# SCH_M5_Stick_YellowBox_Hat_2023-08-26.net
KiCad netlist of a schematic drawn in EasyEDA
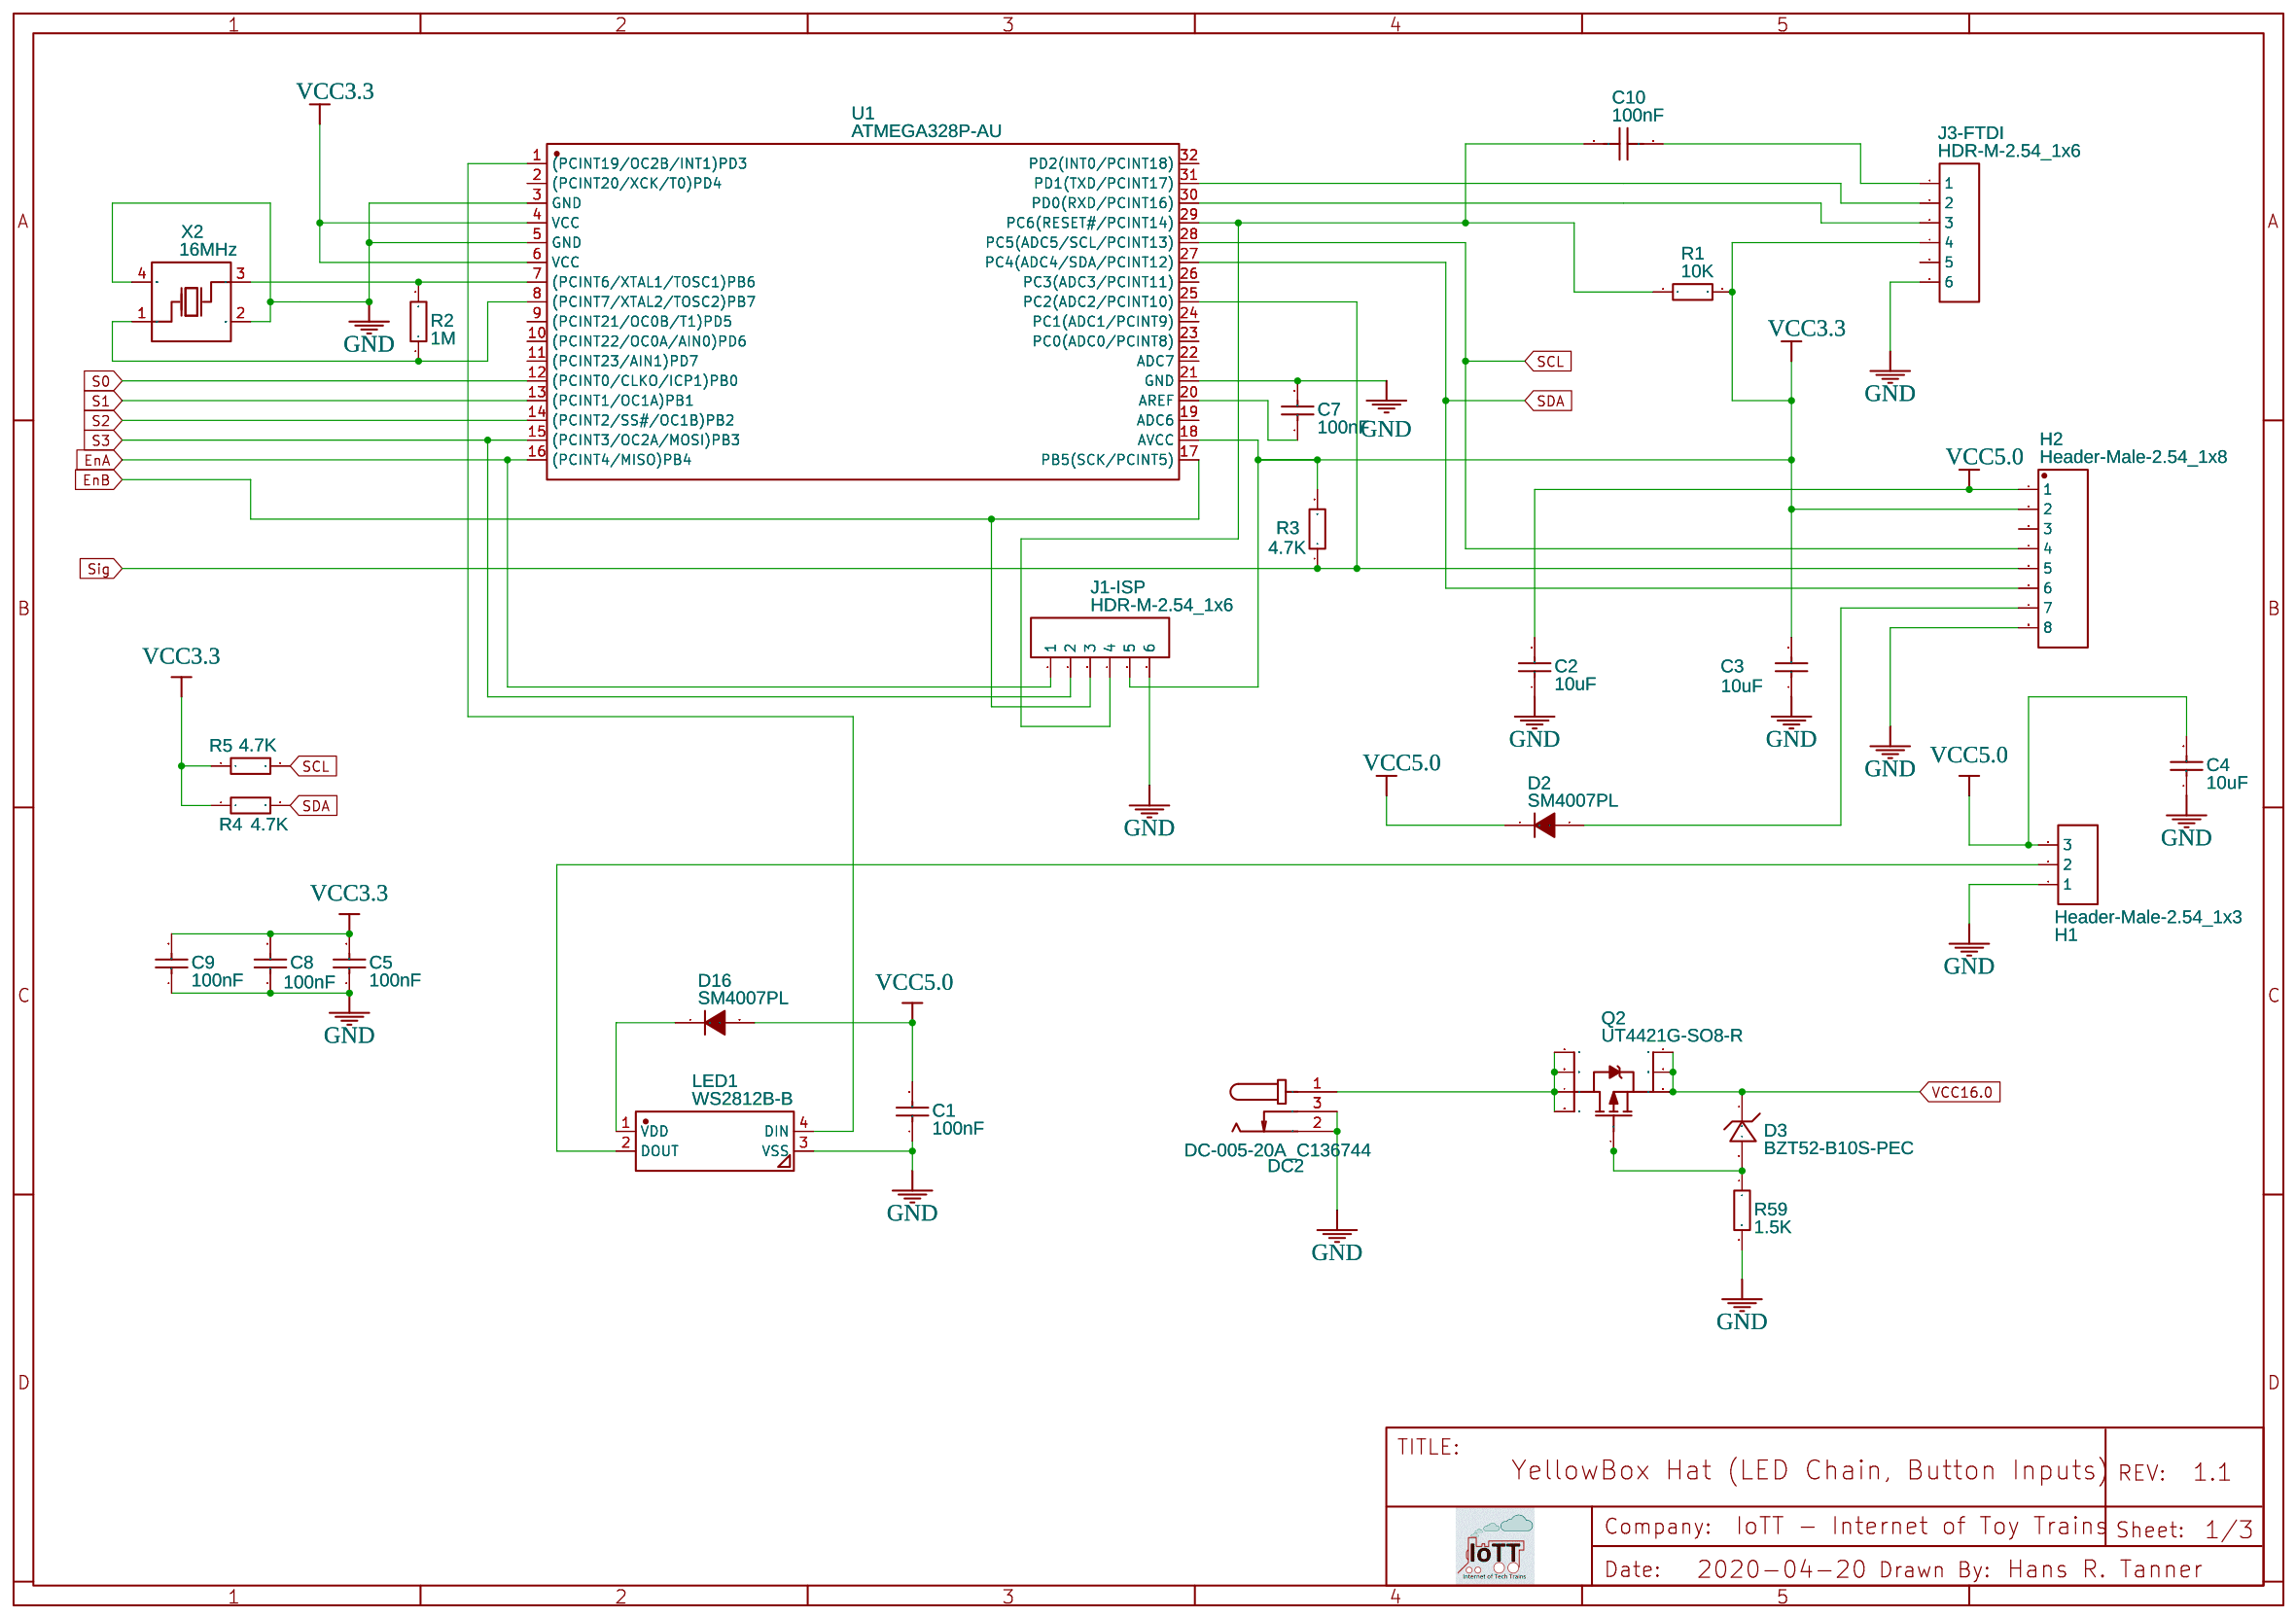
[diagram p0: YellowBox Hat P1]
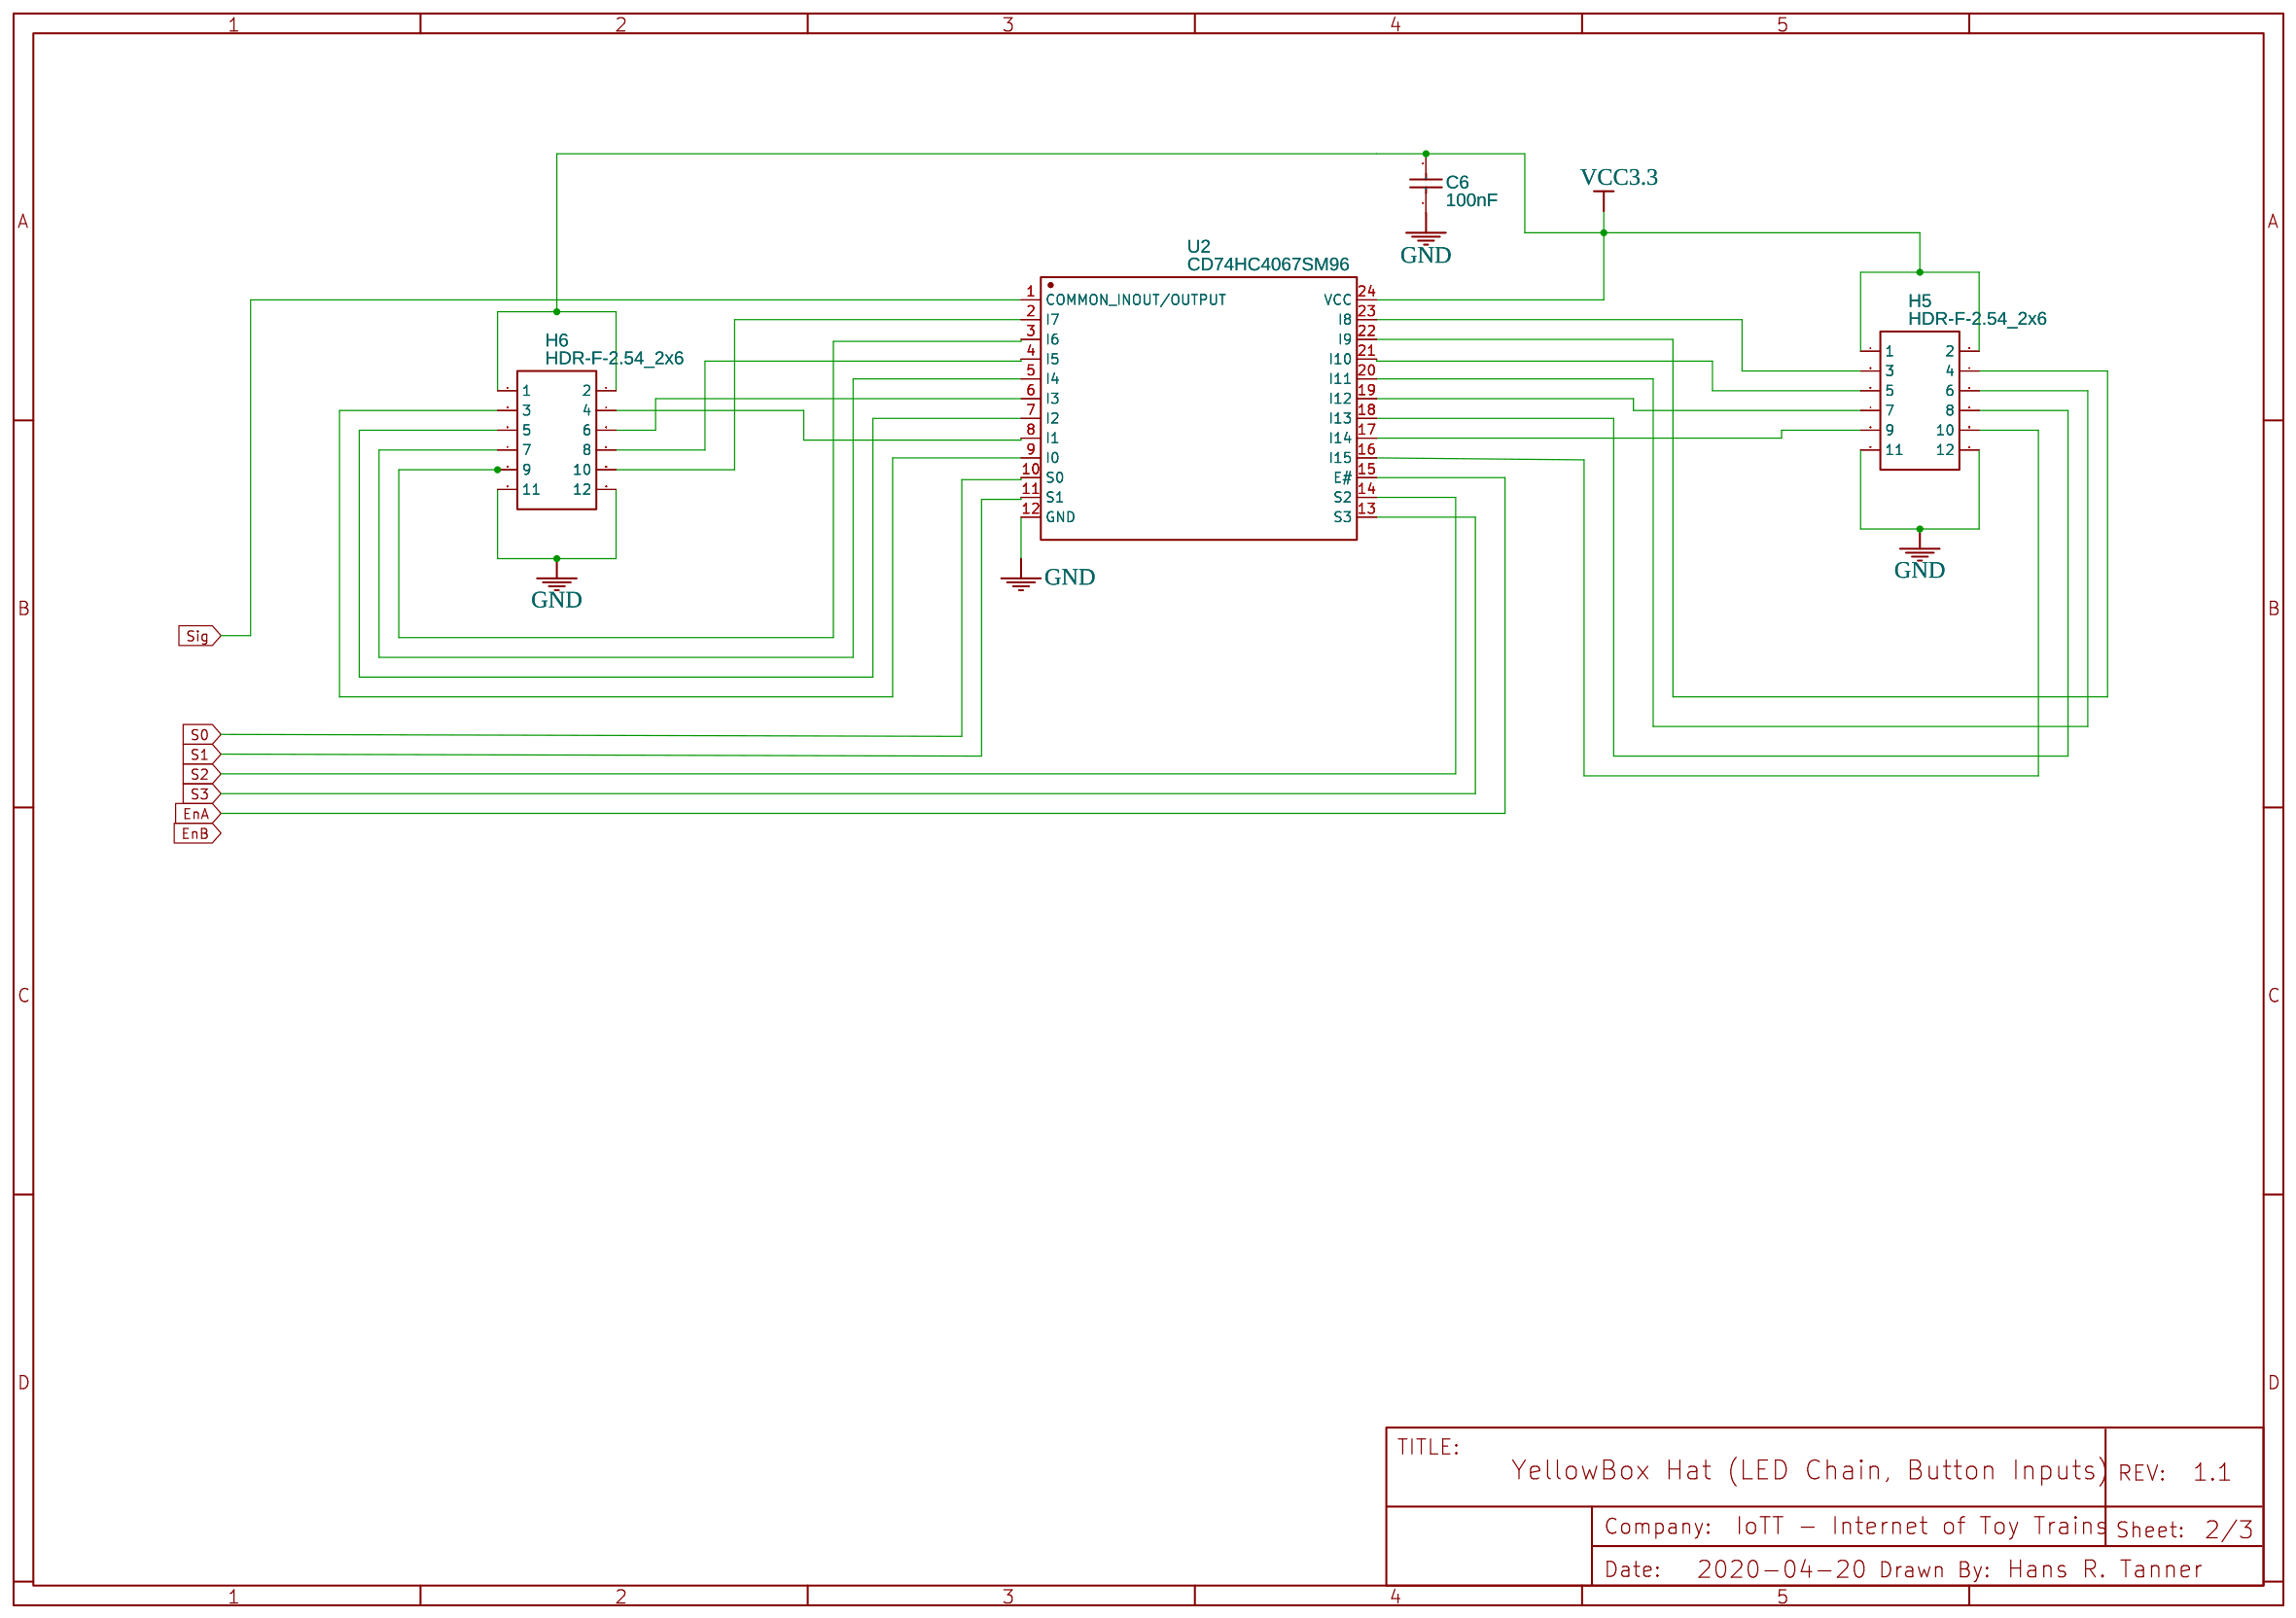
[diagram p1: YellowBox Hat P2]
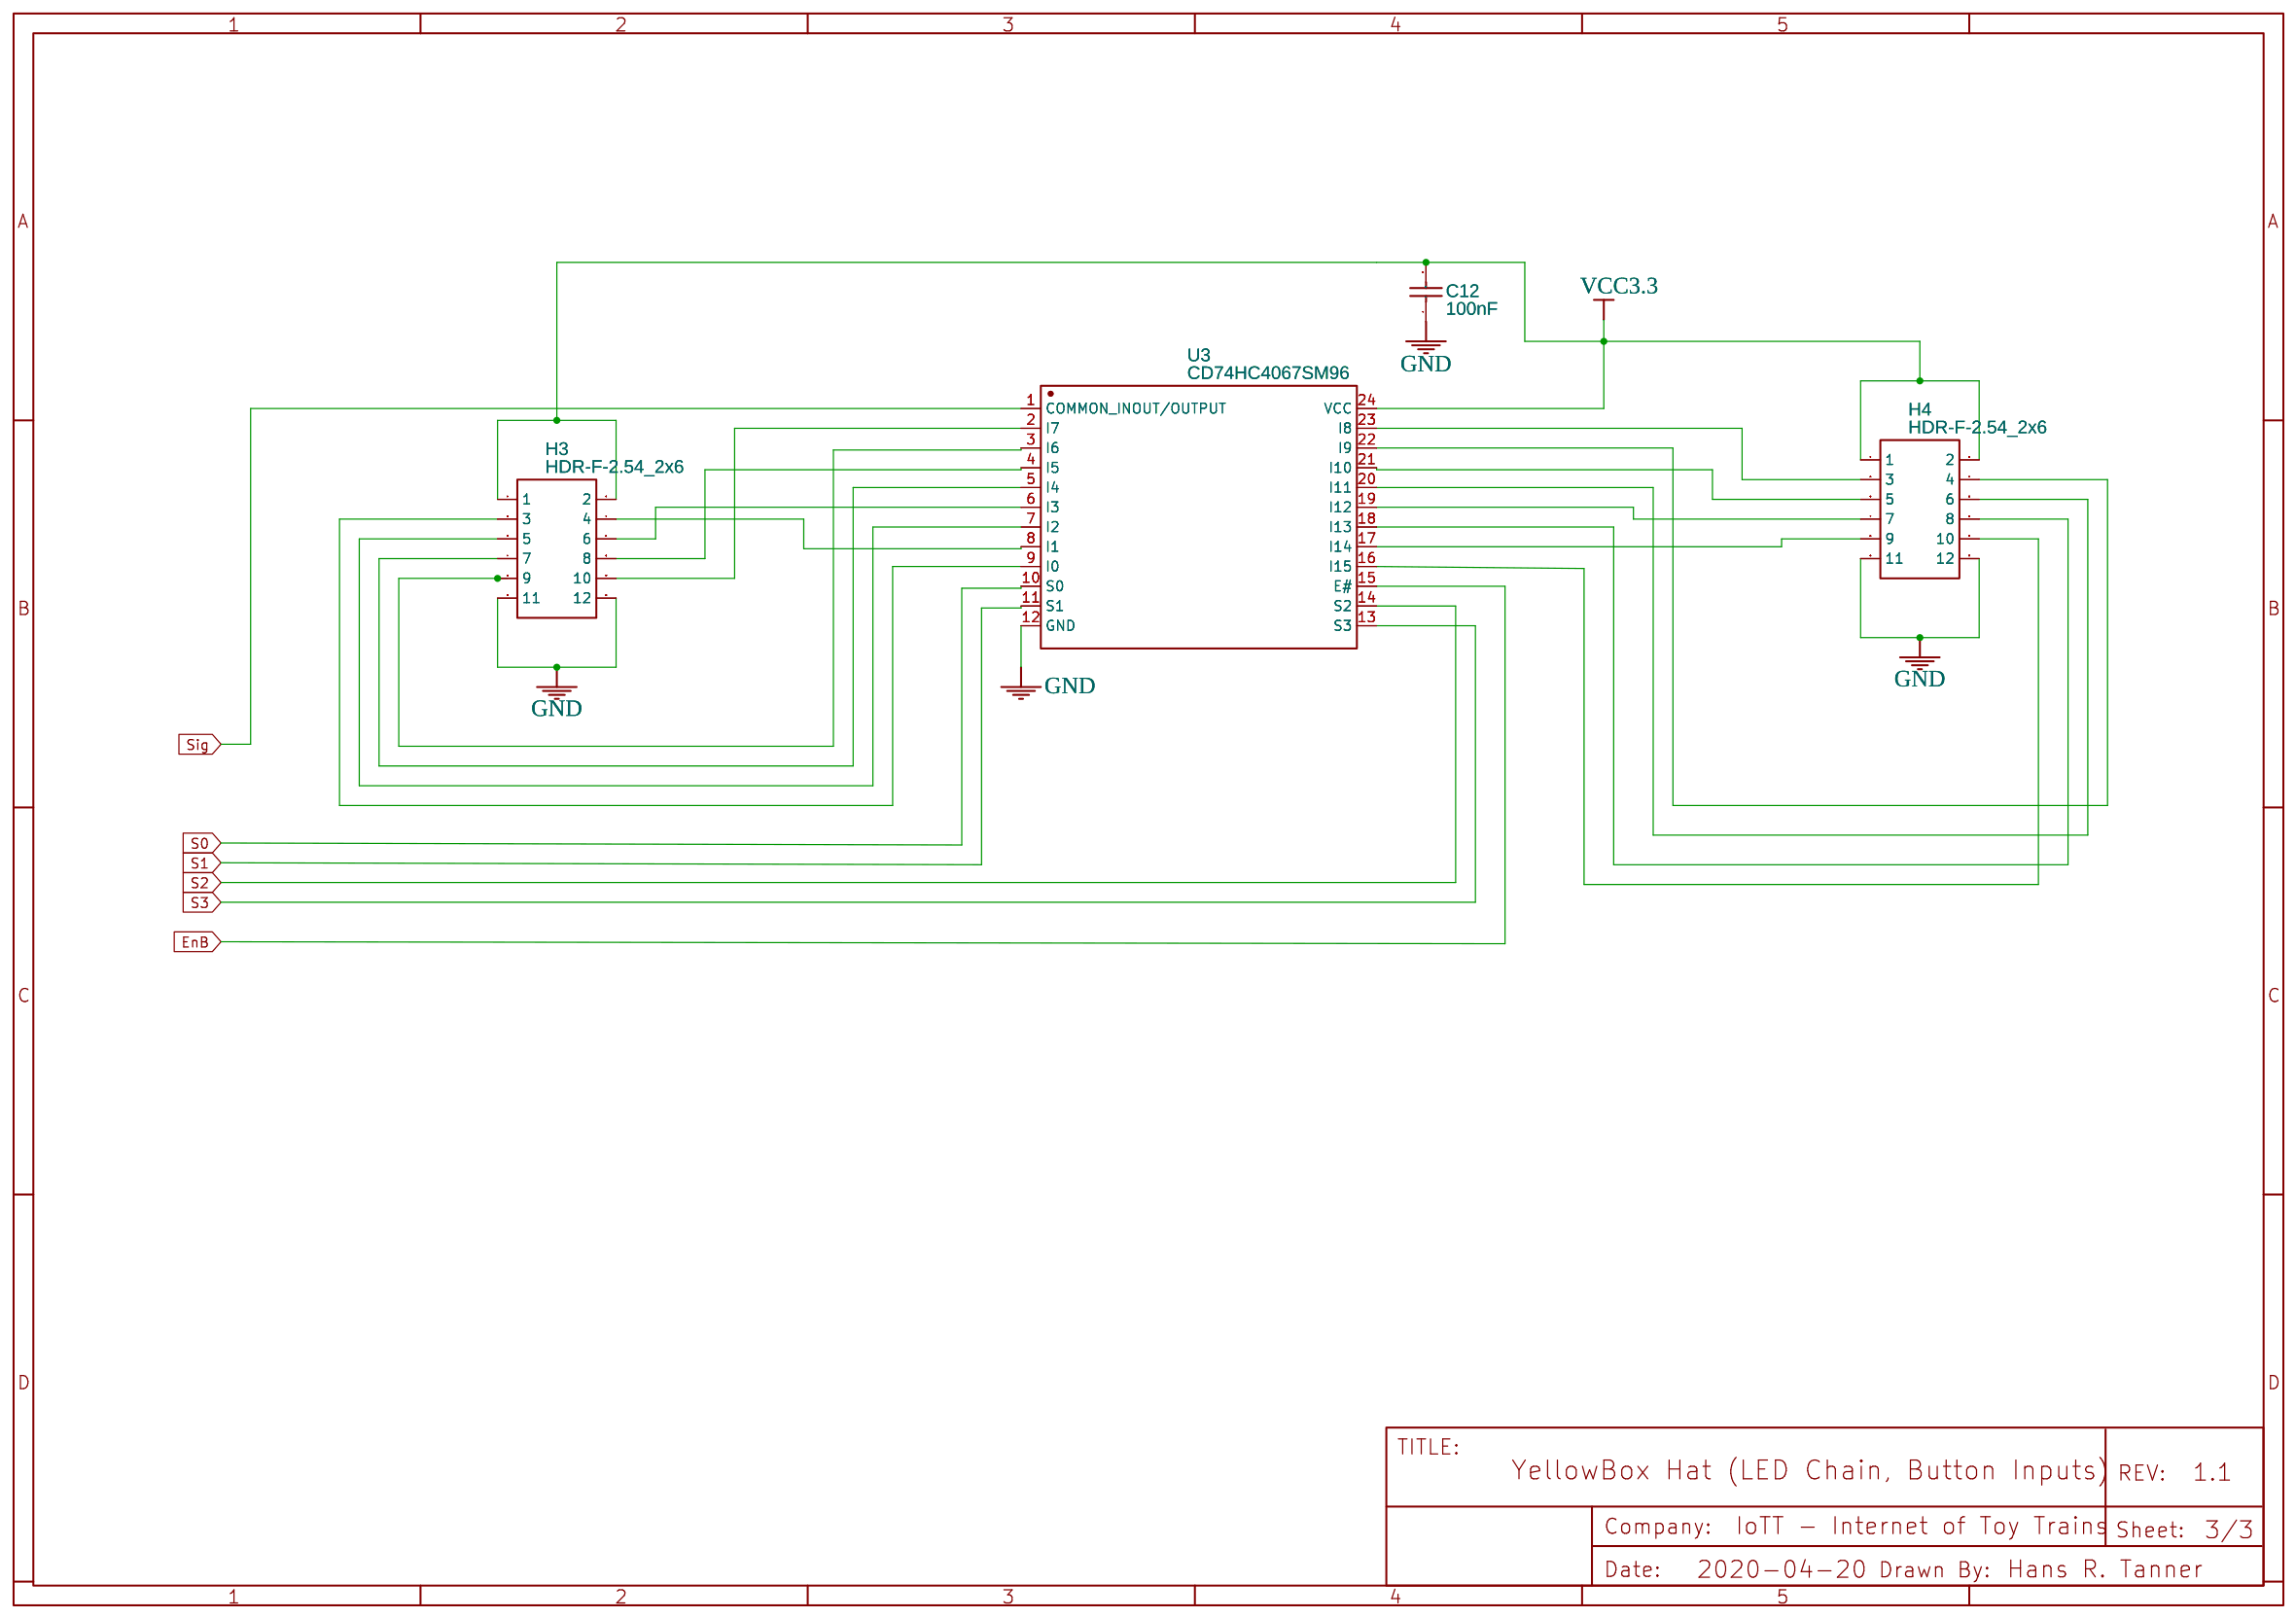
[diagram p2: YellowBox Hat P3]
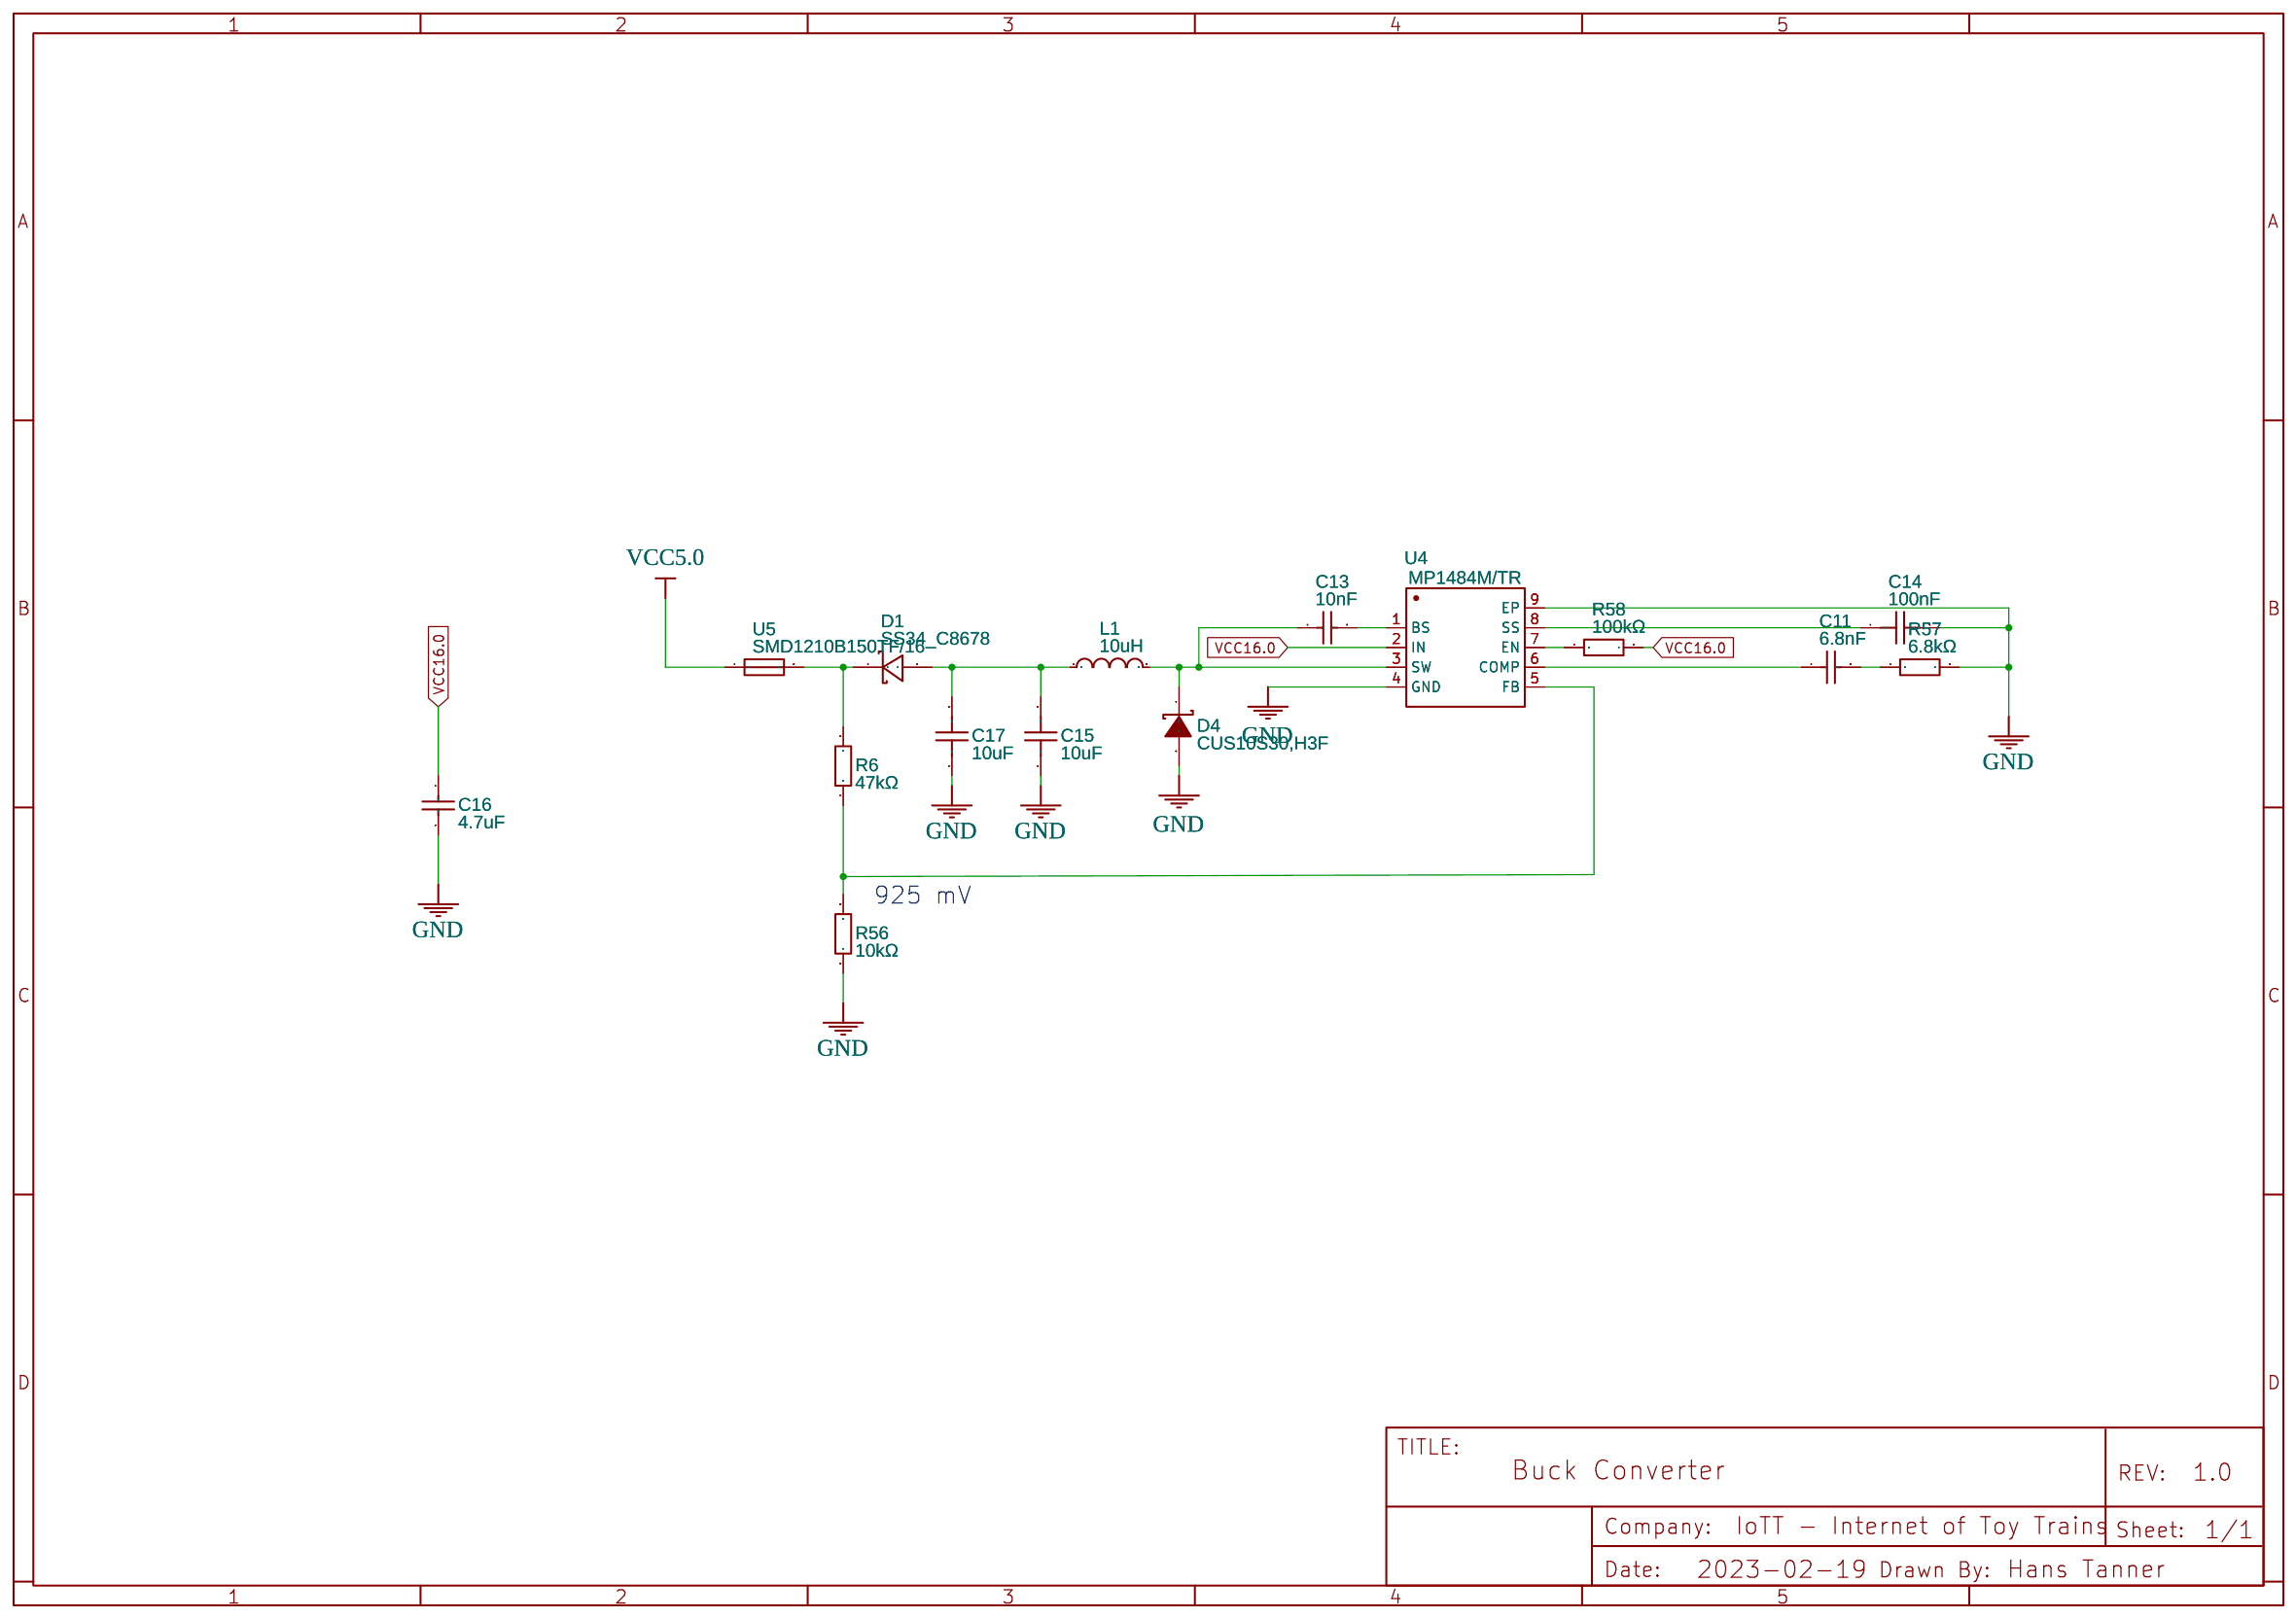
[diagram p3: Buck Converter]

(export (version "E")
  (design (tool "Eeschema 10.0.6"))
  (components
    (comp (ref "C1")
      (value "100nF")
      (fields (field (name "Manufacturer Part") "CL05B104KO5NNNC") (field (name "Manufacturer") "SAMSUNG"))
      (libsource (lib "") (part "CL05B104KO5NNNC"))
    )
    (comp (ref "C2")
      (value "10uF")
      (fields (field (name "Manufacturer Part") "CL21A106KAYNNNE") (field (name "Manufacturer") "SAMSUNG"))
      (libsource (lib "") (part "CL21A106KAYNNNE"))
    )
    (comp (ref "C3")
      (value "10uF")
      (fields (field (name "Manufacturer Part") "CL21A106KAYNNNE") (field (name "Manufacturer") "SAMSUNG"))
      (libsource (lib "") (part "CL21A106KAYNNNE"))
    )
    (comp (ref "C4")
      (value "10uF")
      (fields (field (name "Manufacturer Part") "CL21A106KAYNNNE") (field (name "Manufacturer") "SAMSUNG"))
      (libsource (lib "") (part "CL21A106KAYNNNE"))
    )
    (comp (ref "C5")
      (value "100nF")
      (fields (field (name "Manufacturer Part") "CL05B104KO5NNNC") (field (name "Manufacturer") "SAMSUNG"))
      (libsource (lib "") (part "CL05B104KO5NNNC"))
    )
    (comp (ref "C7")
      (value "100nF")
      (fields (field (name "Manufacturer Part") "CL05B104KO5NNNC") (field (name "Manufacturer") "SAMSUNG"))
      (libsource (lib "") (part "CL05B104KO5NNNC"))
    )
    (comp (ref "C8")
      (value "100nF")
      (fields (field (name "Manufacturer Part") "CL05B104KO5NNNC") (field (name "Manufacturer") "SAMSUNG"))
      (libsource (lib "") (part "CL05B104KO5NNNC"))
    )
    (comp (ref "C9")
      (value "100nF")
      (fields (field (name "Manufacturer Part") "CL05B104KO5NNNC") (field (name "Manufacturer") "SAMSUNG"))
      (libsource (lib "") (part "CL05B104KO5NNNC"))
    )
    (comp (ref "C10")
      (value "100nF")
      (fields (field (name "Manufacturer Part") "CC0603KRX7R9BB104") (field (name "Manufacturer") "YAGEO"))
      (libsource (lib "") (part "CC0603KRX7R9BB104"))
    )
    (comp (ref "D2")
      (value "SM4007PL")
      (fields (field (name "Manufacturer") "MDD"))
      (libsource (lib "") (part "SM4007PL"))
    )
    (comp (ref "D3")
      (value "BZT52-B10S-PEC")
      (fields
        (field (name "Manufacturer Part") "BZT52-B10S_R1_00001")
        (field (name "Manufacturer") "PANJIT(强茂)")
      )
      (libsource (lib "") (part "BZT52-B10S-PEC"))
    )
    (comp (ref "D16")
      (value "SM4007PL")
      (fields (field (name "Manufacturer") "MDD"))
      (libsource (lib "") (part "SM4007PL"))
    )
    (comp (ref "DC2")
      (value "DC-005-20A_C136744")
      (fields (field (name "Manufacturer Part") "DC-005-20A") (field (name "Manufacturer") "HRO"))
      (libsource (lib "") (part "DC-005-20A_C136744"))
    )
    (comp (ref "H1")
      (value "Header-Male-2.54_1x3")
      (fields (field (name "Manufacturer Part") "Header2.54mm 1*3P") (field (name "Manufacturer") "BOOMELE"))
      (libsource (lib "") (part "Header-Male-2.54_1x3"))
    )
    (comp (ref "H2")
      (value "Header-Male-2.54_1x8")
      (fields
        (field (name "Manufacturer Part") "210S-1*8P L=11.6MMGold-plated black")
        (field (name "Manufacturer") "Ckmtw")
      )
      (libsource (lib "") (part "Header-Male-2.54_1x8"))
    )
    (comp (ref "J1-ISP") (value "HDR-M-2.54_1x6") (libsource (lib "") (part "HDR-M-2.54_1x6")))
    (comp (ref "J3-FTDI") (value "HDR-M-2.54_1x6") (libsource (lib "") (part "HDR-M-2.54_1x6_1")))
    (comp (ref "LED1")
      (value "WS2812B-B")
      (fields (field (name "Manufacturer") "Worldsemi"))
      (libsource (lib "") (part "WS2812B-B"))
    )
    (comp (ref "Q2")
      (value "UT4421G-SO8-R")
      (fields (field (name "Manufacturer") "UTC(友顺)"))
      (libsource (lib "") (part "UT4421G-SO8-R"))
    )
    (comp (ref "R1")
      (value "10K")
      (fields (field (name "Manufacturer Part") "0402WGF1002TCE") (field (name "Manufacturer") "UniOhm"))
      (libsource (lib "") (part "0402WGF1002TCE"))
    )
    (comp (ref "R2")
      (value "1M")
      (fields (field (name "Manufacturer Part") "0402WGF1004TCE") (field (name "Manufacturer") "UniOhm"))
      (libsource (lib "") (part "0402WGF1004TCE"))
    )
    (comp (ref "R3")
      (value "4.7K")
      (fields (field (name "Manufacturer Part") "0603WAF4701T5E") (field (name "Manufacturer") "UniOhm"))
      (libsource (lib "") (part "0603WAF1001T5E"))
    )
    (comp (ref "R4")
      (value "4.7K")
      (fields (field (name "Manufacturer Part") "0603WAF4701T5E") (field (name "Manufacturer") "UniOhm"))
      (libsource (lib "") (part "0603WAF1001T5E_1"))
    )
    (comp (ref "R5")
      (value "4.7K")
      (fields (field (name "Manufacturer Part") "0603WAF4701T5E") (field (name "Manufacturer") "UniOhm"))
      (libsource (lib "") (part "0603WAF1001T5E_1"))
    )
    (comp (ref "R59")
      (value "1.5K")
      (fields (field (name "Manufacturer Part") "0402WGF1501TCE") (field (name "Manufacturer") "UniOhm"))
      (libsource (lib "") (part "0402WGF1501TCE"))
    )
    (comp (ref "U1")
      (value "ATMEGA328P-AU")
      (fields (field (name "Manufacturer") "MICROCHIP"))
      (libsource (lib "") (part "ATMEGA328P-AU"))
    )
    (comp (ref "X2")
      (value "16MHz")
      (fields (field (name "Manufacturer Part") "X322516MLB4SI") (field (name "Manufacturer") "YXC"))
      (libsource (lib "") (part "X322516MLB4SI"))
    )
    (comp (ref "C6")
      (value "100nF")
      (fields (field (name "Manufacturer Part") "CL05B104KO5NNNC") (field (name "Manufacturer") "SAMSUNG"))
      (libsource (lib "") (part "CL05B104KO5NNNC"))
    )
    (comp (ref "H5") (value "HDR-F-2.54_2x6") (libsource (lib "") (part "HDR-F-2.54_2x6")))
    (comp (ref "H6") (value "HDR-F-2.54_2x6") (libsource (lib "") (part "HDR-F-2.54_2x6")))
    (comp (ref "U2")
      (value "CD74HC4067SM96")
      (fields (field (name "Manufacturer") "TI"))
      (libsource (lib "") (part "CD74HC4067SM96"))
    )
    (comp (ref "C12")
      (value "100nF")
      (fields (field (name "Manufacturer Part") "CL05B104KO5NNNC") (field (name "Manufacturer") "SAMSUNG"))
      (libsource (lib "") (part "CL05B104KO5NNNC"))
    )
    (comp (ref "H3") (value "HDR-F-2.54_2x6") (libsource (lib "") (part "HDR-F-2.54_2x6")))
    (comp (ref "H4") (value "HDR-F-2.54_2x6") (libsource (lib "") (part "HDR-F-2.54_2x6")))
    (comp (ref "U3")
      (value "CD74HC4067SM96")
      (fields (field (name "Manufacturer") "TI"))
      (libsource (lib "") (part "CD74HC4067SM96"))
    )
    (comp (ref "C11")
      (value "6.8nF")
      (fields (field (name "Manufacturer Part") "0402B682K500NT") (field (name "Manufacturer") "FH(风华)"))
      (libsource (lib "") (part "0402B682K500NT"))
    )
    (comp (ref "C13")
      (value "10nF")
      (fields
        (field (name "Manufacturer Part") "CL05B103KB5NNNC")
        (field (name "Manufacturer") "SAMSUNG(三星)")
      )
      (libsource (lib "") (part "CL05B103KB5NNNC"))
    )
    (comp (ref "C14")
      (value "100nF")
      (fields
        (field (name "Manufacturer Part") "CL05B104KB54PNC")
        (field (name "Manufacturer") "SAMSUNG(三星)")
      )
      (libsource (lib "") (part "CL05B104KB54PNC"))
    )
    (comp (ref "C15")
      (value "10uF")
      (fields
        (field (name "Manufacturer Part") "CL10A106KP8NNNC")
        (field (name "Manufacturer") "SAMSUNG(三星)")
      )
      (libsource (lib "") (part "CL10A106KP8NNNC"))
    )
    (comp (ref "C16")
      (value "4.7uF")
      (fields (field (name "Manufacturer Part") "1206B475K500NT") (field (name "Manufacturer") "FH(风华)"))
      (libsource (lib "") (part "1206B475K500NT"))
    )
    (comp (ref "C17")
      (value "10uF")
      (fields
        (field (name "Manufacturer Part") "CL10A106KP8NNNC")
        (field (name "Manufacturer") "SAMSUNG(三星)")
      )
      (libsource (lib "") (part "CL10A106KP8NNNC"))
    )
    (comp (ref "D1")
      (value "SS34_C8678")
      (fields (field (name "Manufacturer Part") "SS34") (field (name "Manufacturer") "MDD"))
      (libsource (lib "") (part "SS34_C8678"))
    )
    (comp (ref "D4")
      (value "CUS10S30,H3F")
      (fields (field (name "Manufacturer") "TOSHIBA(东芝)"))
      (libsource (lib "") (part "CUS10S30,H3F"))
    )
    (comp (ref "L1")
      (value "10uH")
      (fields (field (name "Manufacturer Part") "APW12A60M100") (field (name "Manufacturer") "Coilank(驰兴电感)"))
      (libsource (lib "") (part "APW12A60M100"))
    )
    (comp (ref "R6")
      (value "47kΩ")
      (fields
        (field (name "Manufacturer Part") "0402WGF4702TCE")
        (field (name "Manufacturer") "UNI-ROYAL(厚声)")
      )
      (libsource (lib "") (part "0402WGF4702TCE"))
    )
    (comp (ref "R56")
      (value "10kΩ")
      (fields
        (field (name "Manufacturer Part") "0402WGF1002TCE")
        (field (name "Manufacturer") "UNI-ROYAL(厚声)")
      )
      (libsource (lib "") (part "0402WGF1002TCE"))
    )
    (comp (ref "R57")
      (value "6.8kΩ")
      (fields
        (field (name "Manufacturer Part") "0402WGF6801TCE")
        (field (name "Manufacturer") "UNI-ROYAL(厚声)")
      )
      (libsource (lib "") (part "0402WGF6801TCE"))
    )
    (comp (ref "R58")
      (value "100kΩ")
      (fields
        (field (name "Manufacturer Part") "0402WGF1003TCE")
        (field (name "Manufacturer") "UNI-ROYAL(厚声)")
      )
      (libsource (lib "") (part "0402WGF1003TCE"))
    )
    (comp (ref "U4")
      (value "MP1484M/TR")
      (fields (field (name "Manufacturer") "HGSEMI(华冠)"))
      (libsource (lib "") (part "MP1484M/TR"))
    )
    (comp (ref "U5")
      (value "SMD1210B150TF/16")
      (fields (field (name "Manufacturer") "Brightking(君耀电子)"))
      (libsource (lib "") (part "SMD1210B150TF/16"))
    )
  )
  (nets
    (net (code "1") (name "EnA") (class "Default")
      (node (ref "J1-ISP") (pin "1") (pinfunction "1_1") (pintype "input"))
      (node (ref "U1") (pin "16") (pinfunction "(PCINT4/MISO)PB4_16") (pintype "unspecified"))
      (node (ref "U2") (pin "15") (pinfunction "E#_15") (pintype "unspecified"))
    )
    (net (code "2") (name "EnB") (class "Default")
      (node (ref "J1-ISP") (pin "3") (pinfunction "3_3") (pintype "input"))
      (node (ref "U1") (pin "17") (pinfunction "PB5(SCK/PCINT5)_17") (pintype "unspecified"))
      (node (ref "U3") (pin "15") (pinfunction "E#_15") (pintype "unspecified"))
    )
    (net (code "3") (name "GND") (class "Default")
      (node (ref "C1") (pin "1") (pinfunction "1_1") (pintype "input"))
      (node (ref "C12") (pin "1") (pinfunction "1_1") (pintype "input"))
      (node (ref "C14") (pin "2") (pinfunction "2_2") (pintype "unspecified"))
      (node (ref "C15") (pin "1") (pinfunction "1_1") (pintype "unspecified"))
      (node (ref "C16") (pin "2") (pinfunction "2_2") (pintype "input"))
      (node (ref "C17") (pin "1") (pinfunction "1_1") (pintype "unspecified"))
      (node (ref "C2") (pin "1") (pinfunction "1_1") (pintype "input"))
      (node (ref "C3") (pin "1") (pinfunction "1_1") (pintype "input"))
      (node (ref "C4") (pin "1") (pinfunction "1_1") (pintype "input"))
      (node (ref "C5") (pin "1") (pinfunction "1_1") (pintype "input"))
      (node (ref "C6") (pin "1") (pinfunction "1_1") (pintype "input"))
      (node (ref "C7") (pin "2") (pinfunction "2_2") (pintype "input"))
      (node (ref "C8") (pin "1") (pinfunction "1_1") (pintype "input"))
      (node (ref "C9") (pin "1") (pinfunction "1_1") (pintype "input"))
      (node (ref "D4") (pin "2") (pinfunction "A_2") (pintype "unspecified"))
      (node (ref "DC2") (pin "2") (pinfunction "2_2") (pintype "unspecified"))
      (node (ref "DC2") (pin "3") (pinfunction "3_3") (pintype "unspecified"))
      (node (ref "H1") (pin "1") (pinfunction "1_1") (pintype "input"))
      (node (ref "H2") (pin "8") (pinfunction "8_8") (pintype "unspecified"))
      (node (ref "H3") (pin "11") (pinfunction "11_11") (pintype "input"))
      (node (ref "H3") (pin "12") (pinfunction "12_12") (pintype "input"))
      (node (ref "H4") (pin "11") (pinfunction "11_11") (pintype "input"))
      (node (ref "H4") (pin "12") (pinfunction "12_12") (pintype "input"))
      (node (ref "H5") (pin "11") (pinfunction "11_11") (pintype "input"))
      (node (ref "H5") (pin "12") (pinfunction "12_12") (pintype "input"))
      (node (ref "H6") (pin "11") (pinfunction "11_11") (pintype "input"))
      (node (ref "H6") (pin "12") (pinfunction "12_12") (pintype "input"))
      (node (ref "J1-ISP") (pin "6") (pinfunction "6_6") (pintype "input"))
      (node (ref "J3-FTDI") (pin "6") (pinfunction "6_6") (pintype "input"))
      (node (ref "LED1") (pin "3") (pinfunction "VSS_3") (pintype "unspecified"))
      (node (ref "R56") (pin "1") (pinfunction "1_1") (pintype "input"))
      (node (ref "R57") (pin "2") (pinfunction "2_2") (pintype "input"))
      (node (ref "R59") (pin "2") (pinfunction "2_2") (pintype "input"))
      (node (ref "U1") (pin "21") (pinfunction "GND_21") (pintype "unspecified"))
      (node (ref "U1") (pin "3") (pinfunction "GND_3") (pintype "unspecified"))
      (node (ref "U1") (pin "5") (pinfunction "GND_5") (pintype "unspecified"))
      (node (ref "U2") (pin "12") (pinfunction "GND_12") (pintype "unspecified"))
      (node (ref "U3") (pin "12") (pinfunction "GND_12") (pintype "unspecified"))
      (node (ref "U4") (pin "4") (pinfunction "GND_4") (pintype "unspecified"))
      (node (ref "U4") (pin "9") (pinfunction "EP_9") (pintype "unspecified"))
      (node (ref "X2") (pin "2") (pinfunction "GND_2") (pintype "unspecified"))
      (node (ref "X2") (pin "4") (pinfunction "GND_4") (pintype "unspecified"))
    )
    (net (code "4") (name "Net-(C10-Pad2)") (class "Default")
      (node (ref "C10") (pin "2") (pinfunction "2_2") (pintype "unspecified"))
      (node (ref "J3-FTDI") (pin "1") (pinfunction "1_1") (pintype "input"))
    )
    (net (code "5") (name "Net-(C11-Pad2)") (class "Default")
      (node (ref "C11") (pin "2") (pinfunction "2_2") (pintype "input"))
      (node (ref "R57") (pin "1") (pinfunction "1_1") (pintype "input"))
    )
    (net (code "6") (name "Net-(D1-A)") (class "Default")
      (node (ref "C15") (pin "2") (pinfunction "2_2") (pintype "unspecified"))
      (node (ref "C17") (pin "2") (pinfunction "2_2") (pintype "unspecified"))
      (node (ref "D1") (pin "2") (pinfunction "A_2") (pintype "unspecified"))
      (node (ref "L1") (pin "1") (pinfunction "1_1") (pintype "unspecified"))
    )
    (net (code "7") (name "Net-(D1-K)") (class "Default")
      (node (ref "D1") (pin "1") (pinfunction "K_1") (pintype "unspecified"))
      (node (ref "R6") (pin "2") (pinfunction "2_2") (pintype "input"))
      (node (ref "U5") (pin "2") (pinfunction "2_2") (pintype "unspecified"))
    )
    (net (code "8") (name "Net-(D2-A)") (class "Default")
      (node (ref "D2") (pin "2") (pinfunction "A_2") (pintype "unspecified"))
      (node (ref "H2") (pin "7") (pinfunction "7_7") (pintype "unspecified"))
    )
    (net (code "9") (name "Net-(D3-A)") (class "Default")
      (node (ref "D3") (pin "2") (pinfunction "A_2") (pintype "unspecified"))
      (node (ref "Q2") (pin "4") (pinfunction "G_4") (pintype "unspecified"))
      (node (ref "R59") (pin "1") (pinfunction "1_1") (pintype "input"))
    )
    (net (code "10") (name "Net-(D4-K)") (class "Default")
      (node (ref "C13") (pin "1") (pinfunction "1_1") (pintype "input"))
      (node (ref "D4") (pin "1") (pinfunction "K_1") (pintype "unspecified"))
      (node (ref "L1") (pin "2") (pinfunction "2_2") (pintype "unspecified"))
      (node (ref "U4") (pin "3") (pinfunction "SW_3") (pintype "unspecified"))
    )
    (net (code "11") (name "Net-(D16-C)") (class "Default")
      (node (ref "D16") (pin "1") (pinfunction "C_1") (pintype "unspecified"))
      (node (ref "LED1") (pin "1") (pinfunction "VDD_1") (pintype "unspecified"))
    )
    (net (code "12") (name "Net-(DC2-Pad1)") (class "Default")
      (node (ref "DC2") (pin "1") (pinfunction "1_1") (pintype "unspecified"))
      (node (ref "Q2") (pin "5") (pinfunction "D_5") (pintype "unspecified"))
      (node (ref "Q2") (pin "6") (pinfunction "D_6") (pintype "unspecified"))
      (node (ref "Q2") (pin "7") (pinfunction "D_7") (pintype "unspecified"))
      (node (ref "Q2") (pin "8") (pinfunction "D_8") (pintype "unspecified"))
    )
    (net (code "13") (name "Net-(LED1-DIN)") (class "Default")
      (node (ref "LED1") (pin "4") (pinfunction "DIN_4") (pintype "unspecified"))
      (node (ref "U1") (pin "1") (pinfunction "(PCINT19/OC2B/INT1)PD3_1") (pintype "unspecified"))
    )
    (net (code "14") (name "Net-(LED1-DOUT)") (class "Default")
      (node (ref "H1") (pin "2") (pinfunction "2_2") (pintype "input"))
      (node (ref "LED1") (pin "2") (pinfunction "DOUT_2") (pintype "unspecified"))
    )
    (net (code "15") (name "Net-(U1-(PCINT6{slash}XTAL1{slash}TOSC1)PB6)") (class "Default")
      (node (ref "R2") (pin "2") (pinfunction "2_2") (pintype "input"))
      (node (ref "U1") (pin "7") (pinfunction "(PCINT6/XTAL1/TOSC1)PB6_7") (pintype "unspecified"))
      (node (ref "X2") (pin "3") (pinfunction "OSC2_3") (pintype "unspecified"))
    )
    (net (code "16") (name "Net-(U1-(PCINT7{slash}XTAL2{slash}TOSC2)PB7)") (class "Default")
      (node (ref "R2") (pin "1") (pinfunction "1_1") (pintype "input"))
      (node (ref "U1") (pin "8") (pinfunction "(PCINT7/XTAL2/TOSC2)PB7_8") (pintype "unspecified"))
      (node (ref "X2") (pin "1") (pinfunction "OSC1_1") (pintype "unspecified"))
    )
    (net (code "17") (name "Net-(U1-AREF)") (class "Default")
      (node (ref "C7") (pin "1") (pinfunction "1_1") (pintype "input"))
      (node (ref "U1") (pin "20") (pinfunction "AREF_20") (pintype "unspecified"))
    )
    (net (code "18") (name "Net-(U1-PC6(RESET#{slash}PCINT14))") (class "Default")
      (node (ref "C10") (pin "1") (pinfunction "1_1") (pintype "unspecified"))
      (node (ref "J1-ISP") (pin "4") (pinfunction "4_4") (pintype "input"))
      (node (ref "R1") (pin "1") (pinfunction "1_1") (pintype "input"))
      (node (ref "U1") (pin "29") (pinfunction "PC6(RESET#/PCINT14)_29") (pintype "unspecified"))
    )
    (net (code "19") (name "Net-(U1-PD0(RXD{slash}PCINT16))") (class "Default")
      (node (ref "J3-FTDI") (pin "3") (pinfunction "3_3") (pintype "input"))
      (node (ref "U1") (pin "30") (pinfunction "PD0(RXD/PCINT16)_30") (pintype "unspecified"))
    )
    (net (code "20") (name "Net-(U1-PD1(TXD{slash}PCINT17))") (class "Default")
      (node (ref "J3-FTDI") (pin "2") (pinfunction "2_2") (pintype "input"))
      (node (ref "U1") (pin "31") (pinfunction "PD1(TXD/PCINT17)_31") (pintype "unspecified"))
    )
    (net (code "21") (name "Net-(U2-I0)") (class "Default")
      (node (ref "H6") (pin "3") (pinfunction "3_3") (pintype "input"))
      (node (ref "U2") (pin "9") (pinfunction "I0_9") (pintype "unspecified"))
    )
    (net (code "22") (name "Net-(U2-I1)") (class "Default")
      (node (ref "H6") (pin "4") (pinfunction "4_4") (pintype "input"))
      (node (ref "U2") (pin "8") (pinfunction "I1_8") (pintype "unspecified"))
    )
    (net (code "23") (name "Net-(U2-I2)") (class "Default")
      (node (ref "H6") (pin "5") (pinfunction "5_5") (pintype "input"))
      (node (ref "U2") (pin "7") (pinfunction "I2_7") (pintype "unspecified"))
    )
    (net (code "24") (name "Net-(U2-I3)") (class "Default")
      (node (ref "H6") (pin "6") (pinfunction "6_6") (pintype "input"))
      (node (ref "U2") (pin "6") (pinfunction "I3_6") (pintype "unspecified"))
    )
    (net (code "25") (name "Net-(U2-I4)") (class "Default")
      (node (ref "H6") (pin "7") (pinfunction "7_7") (pintype "input"))
      (node (ref "U2") (pin "5") (pinfunction "I4_5") (pintype "unspecified"))
    )
    (net (code "26") (name "Net-(U2-I5)") (class "Default")
      (node (ref "H6") (pin "8") (pinfunction "8_8") (pintype "input"))
      (node (ref "U2") (pin "4") (pinfunction "I5_4") (pintype "unspecified"))
    )
    (net (code "27") (name "Net-(U2-I6)") (class "Default")
      (node (ref "H6") (pin "9") (pinfunction "9_9") (pintype "input"))
      (node (ref "U2") (pin "3") (pinfunction "I6_3") (pintype "unspecified"))
    )
    (net (code "28") (name "Net-(U2-I7)") (class "Default")
      (node (ref "H6") (pin "10") (pinfunction "10_10") (pintype "input"))
      (node (ref "U2") (pin "2") (pinfunction "I7_2") (pintype "unspecified"))
    )
    (net (code "29") (name "Net-(U2-I8)") (class "Default")
      (node (ref "H5") (pin "3") (pinfunction "3_3") (pintype "input"))
      (node (ref "U2") (pin "23") (pinfunction "I8_23") (pintype "unspecified"))
    )
    (net (code "30") (name "Net-(U2-I9)") (class "Default")
      (node (ref "H5") (pin "4") (pinfunction "4_4") (pintype "input"))
      (node (ref "U2") (pin "22") (pinfunction "I9_22") (pintype "unspecified"))
    )
    (net (code "31") (name "Net-(U2-I10)") (class "Default")
      (node (ref "H5") (pin "5") (pinfunction "5_5") (pintype "input"))
      (node (ref "U2") (pin "21") (pinfunction "I10_21") (pintype "unspecified"))
    )
    (net (code "32") (name "Net-(U2-I11)") (class "Default")
      (node (ref "H5") (pin "6") (pinfunction "6_6") (pintype "input"))
      (node (ref "U2") (pin "20") (pinfunction "I11_20") (pintype "unspecified"))
    )
    (net (code "33") (name "Net-(U2-I12)") (class "Default")
      (node (ref "H5") (pin "7") (pinfunction "7_7") (pintype "input"))
      (node (ref "U2") (pin "19") (pinfunction "I12_19") (pintype "unspecified"))
    )
    (net (code "34") (name "Net-(U2-I13)") (class "Default")
      (node (ref "H5") (pin "8") (pinfunction "8_8") (pintype "input"))
      (node (ref "U2") (pin "18") (pinfunction "I13_18") (pintype "unspecified"))
    )
    (net (code "35") (name "Net-(U2-I14)") (class "Default")
      (node (ref "H5") (pin "9") (pinfunction "9_9") (pintype "input"))
      (node (ref "U2") (pin "17") (pinfunction "I14_17") (pintype "unspecified"))
    )
    (net (code "36") (name "Net-(U2-I15)") (class "Default")
      (node (ref "H5") (pin "10") (pinfunction "10_10") (pintype "input"))
      (node (ref "U2") (pin "16") (pinfunction "I15_16") (pintype "unspecified"))
    )
    (net (code "37") (name "Net-(U3-I0)") (class "Default")
      (node (ref "H3") (pin "3") (pinfunction "3_3") (pintype "input"))
      (node (ref "U3") (pin "9") (pinfunction "I0_9") (pintype "unspecified"))
    )
    (net (code "38") (name "Net-(U3-I1)") (class "Default")
      (node (ref "H3") (pin "4") (pinfunction "4_4") (pintype "input"))
      (node (ref "U3") (pin "8") (pinfunction "I1_8") (pintype "unspecified"))
    )
    (net (code "39") (name "Net-(U3-I2)") (class "Default")
      (node (ref "H3") (pin "5") (pinfunction "5_5") (pintype "input"))
      (node (ref "U3") (pin "7") (pinfunction "I2_7") (pintype "unspecified"))
    )
    (net (code "40") (name "Net-(U3-I3)") (class "Default")
      (node (ref "H3") (pin "6") (pinfunction "6_6") (pintype "input"))
      (node (ref "U3") (pin "6") (pinfunction "I3_6") (pintype "unspecified"))
    )
    (net (code "41") (name "Net-(U3-I4)") (class "Default")
      (node (ref "H3") (pin "7") (pinfunction "7_7") (pintype "input"))
      (node (ref "U3") (pin "5") (pinfunction "I4_5") (pintype "unspecified"))
    )
    (net (code "42") (name "Net-(U3-I5)") (class "Default")
      (node (ref "H3") (pin "8") (pinfunction "8_8") (pintype "input"))
      (node (ref "U3") (pin "4") (pinfunction "I5_4") (pintype "unspecified"))
    )
    (net (code "43") (name "Net-(U3-I6)") (class "Default")
      (node (ref "H3") (pin "9") (pinfunction "9_9") (pintype "input"))
      (node (ref "U3") (pin "3") (pinfunction "I6_3") (pintype "unspecified"))
    )
    (net (code "44") (name "Net-(U3-I7)") (class "Default")
      (node (ref "H3") (pin "10") (pinfunction "10_10") (pintype "input"))
      (node (ref "U3") (pin "2") (pinfunction "I7_2") (pintype "unspecified"))
    )
    (net (code "45") (name "Net-(U3-I8)") (class "Default")
      (node (ref "H4") (pin "3") (pinfunction "3_3") (pintype "input"))
      (node (ref "U3") (pin "23") (pinfunction "I8_23") (pintype "unspecified"))
    )
    (net (code "46") (name "Net-(U3-I9)") (class "Default")
      (node (ref "H4") (pin "4") (pinfunction "4_4") (pintype "input"))
      (node (ref "U3") (pin "22") (pinfunction "I9_22") (pintype "unspecified"))
    )
    (net (code "47") (name "Net-(U3-I10)") (class "Default")
      (node (ref "H4") (pin "5") (pinfunction "5_5") (pintype "input"))
      (node (ref "U3") (pin "21") (pinfunction "I10_21") (pintype "unspecified"))
    )
    (net (code "48") (name "Net-(U3-I11)") (class "Default")
      (node (ref "H4") (pin "6") (pinfunction "6_6") (pintype "input"))
      (node (ref "U3") (pin "20") (pinfunction "I11_20") (pintype "unspecified"))
    )
    (net (code "49") (name "Net-(U3-I12)") (class "Default")
      (node (ref "H4") (pin "7") (pinfunction "7_7") (pintype "input"))
      (node (ref "U3") (pin "19") (pinfunction "I12_19") (pintype "unspecified"))
    )
    (net (code "50") (name "Net-(U3-I13)") (class "Default")
      (node (ref "H4") (pin "8") (pinfunction "8_8") (pintype "input"))
      (node (ref "U3") (pin "18") (pinfunction "I13_18") (pintype "unspecified"))
    )
    (net (code "51") (name "Net-(U3-I14)") (class "Default")
      (node (ref "H4") (pin "9") (pinfunction "9_9") (pintype "input"))
      (node (ref "U3") (pin "17") (pinfunction "I14_17") (pintype "unspecified"))
    )
    (net (code "52") (name "Net-(U3-I15)") (class "Default")
      (node (ref "H4") (pin "10") (pinfunction "10_10") (pintype "input"))
      (node (ref "U3") (pin "16") (pinfunction "I15_16") (pintype "unspecified"))
    )
    (net (code "53") (name "Net-(U4-BS)") (class "Default")
      (node (ref "C13") (pin "2") (pinfunction "2_2") (pintype "input"))
      (node (ref "U4") (pin "1") (pinfunction "BS_1") (pintype "unspecified"))
    )
    (net (code "54") (name "Net-(U4-COMP)") (class "Default")
      (node (ref "C11") (pin "1") (pinfunction "1_1") (pintype "input"))
      (node (ref "U4") (pin "6") (pinfunction "COMP_6") (pintype "unspecified"))
    )
    (net (code "55") (name "Net-(U4-EN)") (class "Default")
      (node (ref "R58") (pin "1") (pinfunction "1_1") (pintype "input"))
      (node (ref "U4") (pin "7") (pinfunction "EN_7") (pintype "unspecified"))
    )
    (net (code "56") (name "Net-(U4-FB)") (class "Default")
      (node (ref "R56") (pin "2") (pinfunction "2_2") (pintype "input"))
      (node (ref "R6") (pin "1") (pinfunction "1_1") (pintype "input"))
      (node (ref "U4") (pin "5") (pinfunction "FB_5") (pintype "unspecified"))
    )
    (net (code "57") (name "Net-(U4-SS)") (class "Default")
      (node (ref "C14") (pin "1") (pinfunction "1_1") (pintype "unspecified"))
      (node (ref "U4") (pin "8") (pinfunction "SS_8") (pintype "unspecified"))
    )
    (net (code "58") (name "S0") (class "Default")
      (node (ref "U1") (pin "12") (pinfunction "(PCINT0/CLKO/ICP1)PB0_12") (pintype "unspecified"))
      (node (ref "U2") (pin "10") (pinfunction "S0_10") (pintype "unspecified"))
      (node (ref "U3") (pin "10") (pinfunction "S0_10") (pintype "unspecified"))
    )
    (net (code "59") (name "S1") (class "Default")
      (node (ref "U1") (pin "13") (pinfunction "(PCINT1/OC1A)PB1_13") (pintype "unspecified"))
      (node (ref "U2") (pin "11") (pinfunction "S1_11") (pintype "unspecified"))
      (node (ref "U3") (pin "11") (pinfunction "S1_11") (pintype "unspecified"))
    )
    (net (code "60") (name "S2") (class "Default")
      (node (ref "U1") (pin "14") (pinfunction "(PCINT2/SS#/OC1B)PB2_14") (pintype "unspecified"))
      (node (ref "U2") (pin "14") (pinfunction "S2_14") (pintype "unspecified"))
      (node (ref "U3") (pin "14") (pinfunction "S2_14") (pintype "unspecified"))
    )
    (net (code "61") (name "S3") (class "Default")
      (node (ref "J1-ISP") (pin "2") (pinfunction "2_2") (pintype "input"))
      (node (ref "U1") (pin "15") (pinfunction "(PCINT3/OC2A/MOSI)PB3_15") (pintype "unspecified"))
      (node (ref "U2") (pin "13") (pinfunction "S3_13") (pintype "unspecified"))
      (node (ref "U3") (pin "13") (pinfunction "S3_13") (pintype "unspecified"))
    )
    (net (code "62") (name "SCL") (class "Default")
      (node (ref "H2") (pin "4") (pinfunction "4_4") (pintype "unspecified"))
      (node (ref "R5") (pin "2") (pinfunction "2_2") (pintype "input"))
      (node (ref "U1") (pin "28") (pinfunction "PC5(ADC5/SCL/PCINT13)_28") (pintype "unspecified"))
    )
    (net (code "63") (name "SDA") (class "Default")
      (node (ref "H2") (pin "6") (pinfunction "6_6") (pintype "unspecified"))
      (node (ref "R4") (pin "2") (pinfunction "2_2") (pintype "input"))
      (node (ref "U1") (pin "27") (pinfunction "PC4(ADC4/SDA/PCINT12)_27") (pintype "unspecified"))
    )
    (net (code "64") (name "Sig") (class "Default")
      (node (ref "H2") (pin "5") (pinfunction "5_5") (pintype "unspecified"))
      (node (ref "R3") (pin "1") (pinfunction "1_1") (pintype "input"))
      (node (ref "U1") (pin "25") (pinfunction "PC2(ADC2/PCINT10)_25") (pintype "unspecified"))
      (node (ref "U2") (pin "1") (pinfunction "COMMON_INOUT/OUTPUT_1") (pintype "unspecified"))
      (node (ref "U3") (pin "1") (pinfunction "COMMON_INOUT/OUTPUT_1") (pintype "unspecified"))
    )
    (net (code "65") (name "VCC3.3") (class "Default")
      (node (ref "C12") (pin "2") (pinfunction "2_2") (pintype "input"))
      (node (ref "C3") (pin "2") (pinfunction "2_2") (pintype "input"))
      (node (ref "C5") (pin "2") (pinfunction "2_2") (pintype "input"))
      (node (ref "C6") (pin "2") (pinfunction "2_2") (pintype "input"))
      (node (ref "C8") (pin "2") (pinfunction "2_2") (pintype "input"))
      (node (ref "C9") (pin "2") (pinfunction "2_2") (pintype "input"))
      (node (ref "H2") (pin "2") (pinfunction "2_2") (pintype "unspecified"))
      (node (ref "H3") (pin "1") (pinfunction "1_1") (pintype "input"))
      (node (ref "H3") (pin "2") (pinfunction "2_2") (pintype "input"))
      (node (ref "H4") (pin "1") (pinfunction "1_1") (pintype "input"))
      (node (ref "H4") (pin "2") (pinfunction "2_2") (pintype "input"))
      (node (ref "H5") (pin "1") (pinfunction "1_1") (pintype "input"))
      (node (ref "H5") (pin "2") (pinfunction "2_2") (pintype "input"))
      (node (ref "H6") (pin "1") (pinfunction "1_1") (pintype "input"))
      (node (ref "H6") (pin "2") (pinfunction "2_2") (pintype "input"))
      (node (ref "J1-ISP") (pin "5") (pinfunction "5_5") (pintype "input"))
      (node (ref "J3-FTDI") (pin "4") (pinfunction "4_4") (pintype "input"))
      (node (ref "R1") (pin "2") (pinfunction "2_2") (pintype "input"))
      (node (ref "R3") (pin "2") (pinfunction "2_2") (pintype "input"))
      (node (ref "R4") (pin "1") (pinfunction "1_1") (pintype "input"))
      (node (ref "R5") (pin "1") (pinfunction "1_1") (pintype "input"))
      (node (ref "U1") (pin "18") (pinfunction "AVCC_18") (pintype "unspecified"))
      (node (ref "U1") (pin "4") (pinfunction "VCC_4") (pintype "unspecified"))
      (node (ref "U1") (pin "6") (pinfunction "VCC_6") (pintype "unspecified"))
      (node (ref "U2") (pin "24") (pinfunction "VCC_24") (pintype "unspecified"))
      (node (ref "U3") (pin "24") (pinfunction "VCC_24") (pintype "unspecified"))
    )
    (net (code "66") (name "VCC5.0") (class "Default")
      (node (ref "C1") (pin "2") (pinfunction "2_2") (pintype "input"))
      (node (ref "C2") (pin "2") (pinfunction "2_2") (pintype "input"))
      (node (ref "C4") (pin "2") (pinfunction "2_2") (pintype "input"))
      (node (ref "D16") (pin "2") (pinfunction "A_2") (pintype "unspecified"))
      (node (ref "D2") (pin "1") (pinfunction "C_1") (pintype "unspecified"))
      (node (ref "H1") (pin "3") (pinfunction "3_3") (pintype "input"))
      (node (ref "H2") (pin "1") (pinfunction "1_1") (pintype "unspecified"))
      (node (ref "U5") (pin "1") (pinfunction "1_1") (pintype "unspecified"))
    )
    (net (code "67") (name "VCC16.0") (class "Default")
      (node (ref "C16") (pin "1") (pinfunction "1_1") (pintype "input"))
      (node (ref "D3") (pin "1") (pinfunction "C_1") (pintype "unspecified"))
      (node (ref "Q2") (pin "1") (pinfunction "S_1") (pintype "unspecified"))
      (node (ref "Q2") (pin "2") (pinfunction "S_2") (pintype "unspecified"))
      (node (ref "Q2") (pin "3") (pinfunction "S_3") (pintype "unspecified"))
      (node (ref "R58") (pin "2") (pinfunction "2_2") (pintype "input"))
      (node (ref "U4") (pin "2") (pinfunction "IN_2") (pintype "unspecified"))
    )
    (net (code "68") (name "unconnected-(H2-Pad3)") (class "Default")
      (node (ref "H2") (pin "3") (pinfunction "3_3") (pintype "unspecified"))
    )
    (net (code "69") (name "unconnected-(J3-FTDI-Pad5)") (class "Default")
      (node (ref "J3-FTDI") (pin "5") (pinfunction "5_5") (pintype "input"))
    )
    (net (code "70") (name "unconnected-(U1-(PCINT20{slash}XCK{slash}T0)PD4-Pad2)") (class "Default")
      (node (ref "U1") (pin "2") (pinfunction "(PCINT20/XCK/T0)PD4_2") (pintype "unspecified"))
    )
    (net (code "71") (name "unconnected-(U1-(PCINT21{slash}OC0B{slash}T1)PD5-Pad9)") (class "Default")
      (node (ref "U1") (pin "9") (pinfunction "(PCINT21/OC0B/T1)PD5_9") (pintype "unspecified"))
    )
    (net (code "72") (name "unconnected-(U1-(PCINT22{slash}OC0A{slash}AIN0)PD6-Pad10)") (class "Default")
      (node (ref "U1") (pin "10") (pinfunction "(PCINT22/OC0A/AIN0)PD6_10") (pintype "unspecified"))
    )
    (net (code "73") (name "unconnected-(U1-(PCINT23{slash}AIN1)PD7-Pad11)") (class "Default")
      (node (ref "U1") (pin "11") (pinfunction "(PCINT23/AIN1)PD7_11") (pintype "unspecified"))
    )
    (net (code "74") (name "unconnected-(U1-ADC6-Pad19)") (class "Default")
      (node (ref "U1") (pin "19") (pinfunction "ADC6_19") (pintype "unspecified"))
    )
    (net (code "75") (name "unconnected-(U1-ADC7-Pad22)") (class "Default")
      (node (ref "U1") (pin "22") (pinfunction "ADC7_22") (pintype "unspecified"))
    )
    (net (code "76") (name "unconnected-(U1-PC0(ADC0{slash}PCINT8)-Pad23)") (class "Default")
      (node (ref "U1") (pin "23") (pinfunction "PC0(ADC0/PCINT8)_23") (pintype "unspecified"))
    )
    (net (code "77") (name "unconnected-(U1-PC1(ADC1{slash}PCINT9)-Pad24)") (class "Default")
      (node (ref "U1") (pin "24") (pinfunction "PC1(ADC1/PCINT9)_24") (pintype "unspecified"))
    )
    (net (code "78") (name "unconnected-(U1-PC3(ADC3{slash}PCINT11)-Pad26)") (class "Default")
      (node (ref "U1") (pin "26") (pinfunction "PC3(ADC3/PCINT11)_26") (pintype "unspecified"))
    )
    (net (code "79") (name "unconnected-(U1-PD2(INT0{slash}PCINT18)-Pad32)") (class "Default")
      (node (ref "U1") (pin "32") (pinfunction "PD2(INT0/PCINT18)_32") (pintype "unspecified"))
    )
  )
)
